# AJH_100m_ADSR_1_0.net
KiCad netlist of a schematic drawn in EAGLE
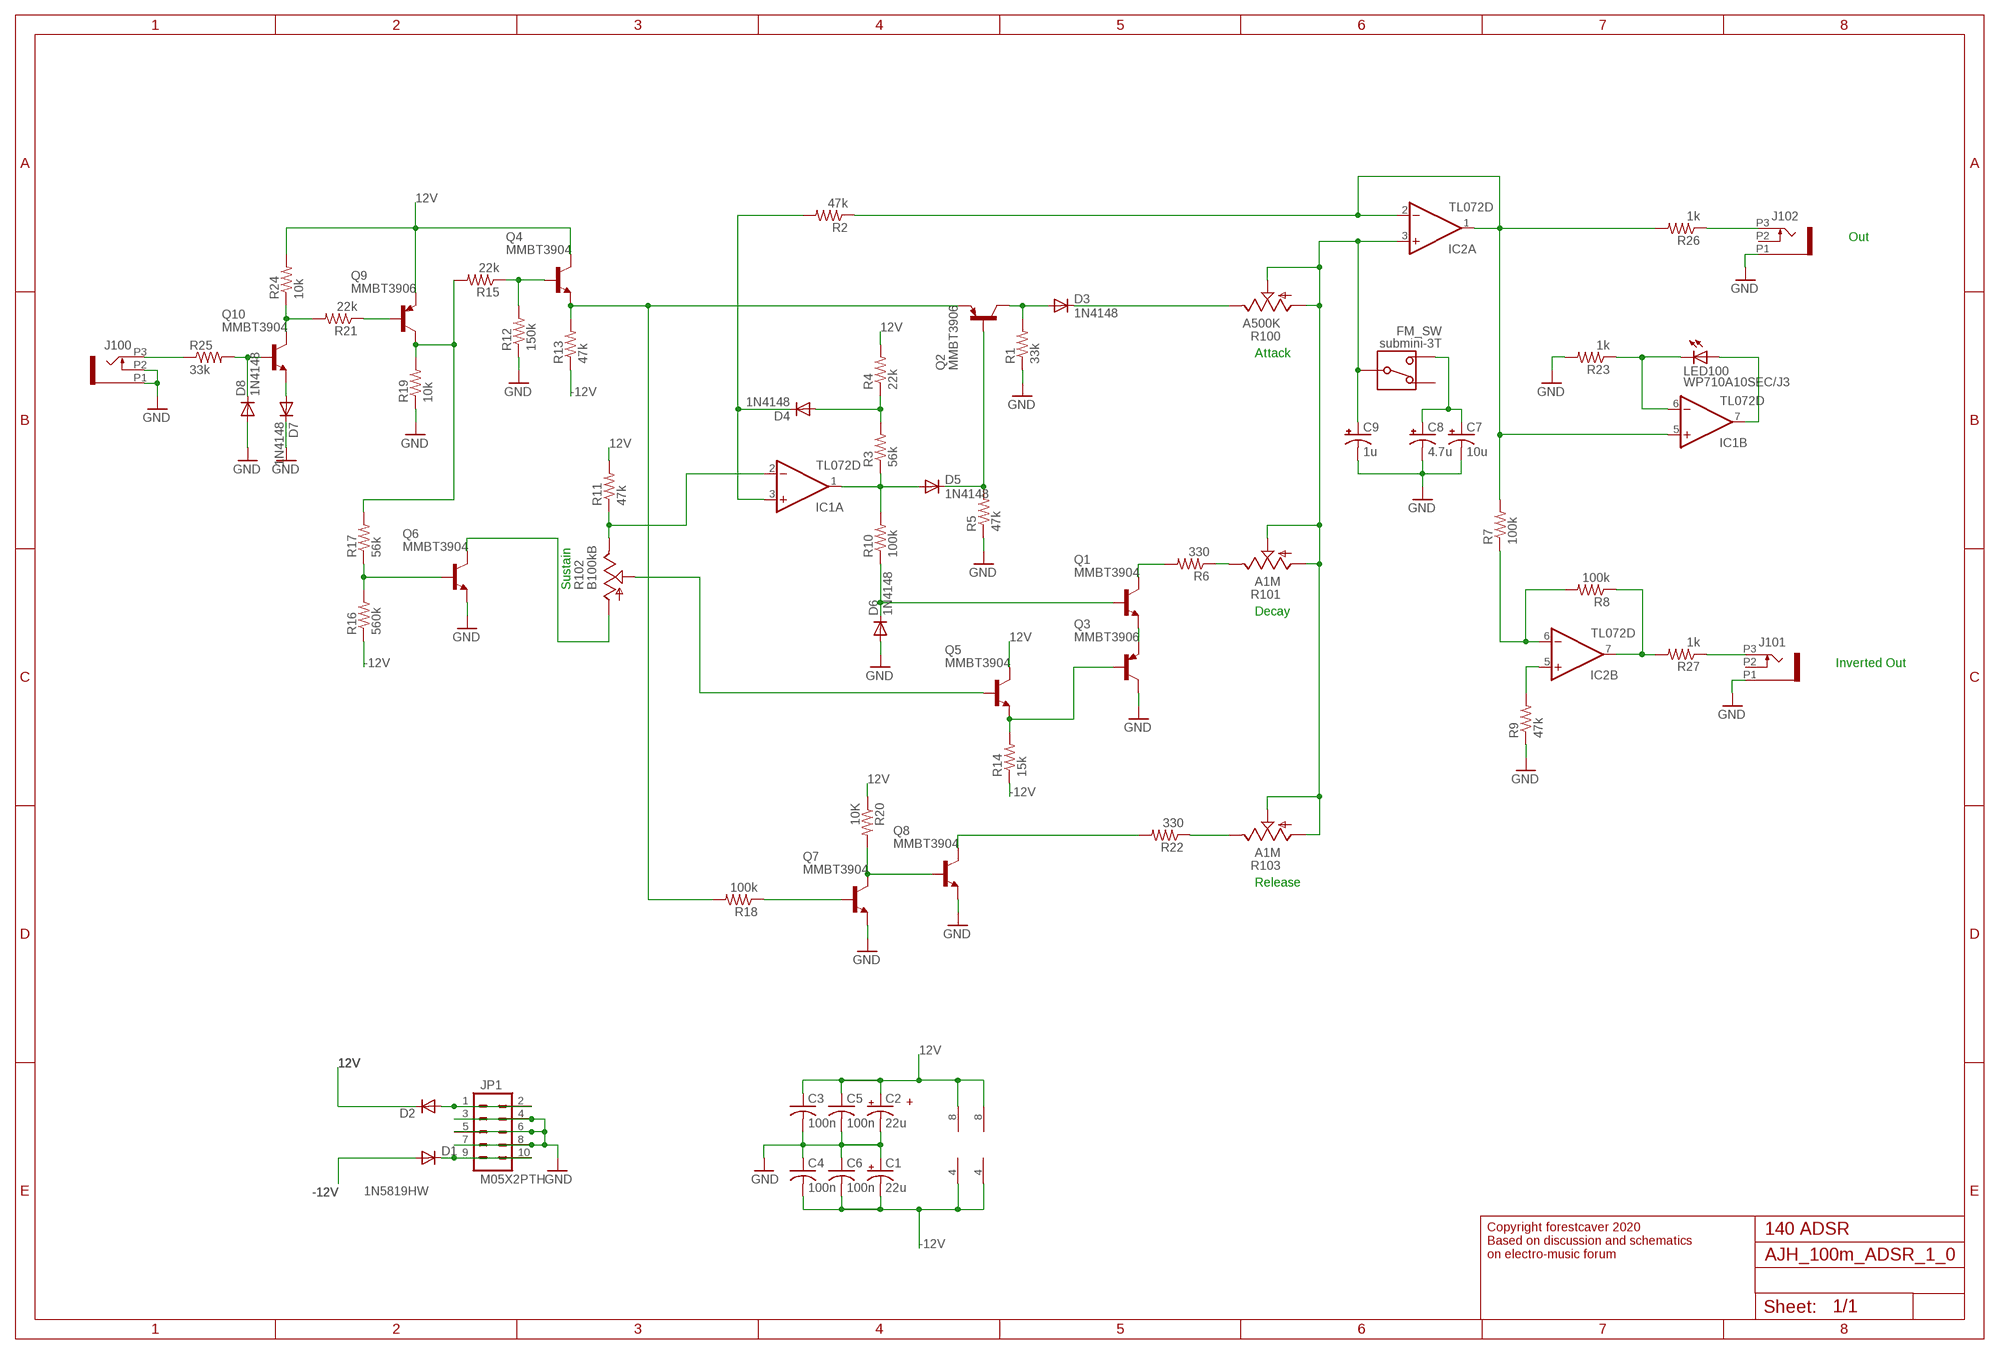
[diagram p0: schematic, sheet 1]

(export (version "E")
  (design (tool "Eeschema 10.0.6"))
  (components
    (comp (ref "C1")
      (value "22u")
      (footprint "eagle-import:PANASONIC_B")
      (libsource (lib "eagle-import") (part "CPOL-USB"))
    )
    (comp (ref "C2")
      (value "22u")
      (footprint "eagle-import:PANASONIC_B")
      (libsource (lib "eagle-import") (part "CPOL-USB"))
    )
    (comp (ref "C3")
      (value "100n")
      (footprint "eagle-import:C0603")
      (libsource (lib "eagle-import") (part "C-USC0603"))
    )
    (comp (ref "C4")
      (value "100n")
      (footprint "eagle-import:C0603")
      (libsource (lib "eagle-import") (part "C-USC0603"))
    )
    (comp (ref "C5")
      (value "100n")
      (footprint "eagle-import:C0603")
      (libsource (lib "eagle-import") (part "C-USC0603"))
    )
    (comp (ref "C6")
      (value "100n")
      (footprint "eagle-import:C0603")
      (libsource (lib "eagle-import") (part "C-USC0603"))
    )
    (comp (ref "C7")
      (value "10u")
      (footprint "eagle-import:PANASONIC_B")
      (libsource (lib "eagle-import") (part "CPOL-USB"))
    )
    (comp (ref "C8")
      (value "4.7u")
      (footprint "eagle-import:PANASONIC_B")
      (libsource (lib "eagle-import") (part "CPOL-USB"))
    )
    (comp (ref "C9")
      (value "1u")
      (footprint "eagle-import:PANASONIC_B")
      (libsource (lib "eagle-import") (part "CPOL-USB"))
    )
    (comp (ref "D1")
      (value "1N5819HW")
      (footprint "eagle-import:SOD123")
      (libsource (lib "eagle-import") (part "DIODE-SOD123"))
    )
    (comp (ref "D2")
      (value "1N5819HW")
      (footprint "eagle-import:SOD123")
      (libsource (lib "eagle-import") (part "DIODE-SOD123"))
    )
    (comp (ref "D3")
      (value "1N4148")
      (footprint "eagle-import:SOD323-W")
      (libsource (lib "eagle-import") (part "DIODE-SOD323-W"))
    )
    (comp (ref "D4")
      (value "1N4148")
      (footprint "eagle-import:SOD323-W")
      (libsource (lib "eagle-import") (part "DIODE-SOD323-W"))
    )
    (comp (ref "D5")
      (value "1N4148")
      (footprint "eagle-import:SOD323-W")
      (libsource (lib "eagle-import") (part "DIODE-SOD323-W"))
    )
    (comp (ref "D6")
      (value "1N4148")
      (footprint "eagle-import:SOD323-W")
      (libsource (lib "eagle-import") (part "DIODE-SOD323-W"))
    )
    (comp (ref "D7")
      (value "1N4148")
      (footprint "eagle-import:SOD323-W")
      (libsource (lib "eagle-import") (part "DIODE-SOD323-W"))
    )
    (comp (ref "D8")
      (value "1N4148")
      (footprint "eagle-import:SOD323-W")
      (libsource (lib "eagle-import") (part "DIODE-SOD323-W"))
    )
    (comp (ref "FM_SW")
      (value "submini-3T")
      (footprint "eagle-import:SPDT-SUB")
      (libsource (lib "eagle-import") (part "SPDTT"))
    )
    (comp (ref "IC1")
      (value "TL072D")
      (footprint "eagle-import:SO08")
      (libsource (lib "eagle-import") (part "TL072D"))
    )
    (comp (ref "IC2")
      (value "TL072D")
      (footprint "eagle-import:SO08")
      (libsource (lib "eagle-import") (part "TL072D"))
    )
    (comp (ref "J100")
      (value "PJ301_THONKICONN6")
      (footprint "eagle-import:WQP_PJ_301M6")
      (libsource (lib "eagle-import") (part "PJ301_THONKICONN6"))
    )
    (comp (ref "J101")
      (value "PJ301_THONKICONN6")
      (footprint "eagle-import:WQP_PJ_301M6")
      (libsource (lib "eagle-import") (part "PJ301_THONKICONN6"))
    )
    (comp (ref "J102")
      (value "PJ301_THONKICONN6")
      (footprint "eagle-import:WQP_PJ_301M6")
      (libsource (lib "eagle-import") (part "PJ301_THONKICONN6"))
    )
    (comp (ref "JP1")
      (value "M05X2PTH")
      (footprint "eagle-import:AVR_ICSP")
      (libsource (lib "eagle-import") (part "M05X2PTH"))
    )
    (comp (ref "LED100")
      (value "WP710A10SEC/J3")
      (footprint "eagle-import:LED3MM")
      (libsource (lib "eagle-import") (part "LED3MM"))
    )
    (comp (ref "Q1")
      (value "MMBT3904")
      (footprint "eagle-import:SOT23-BEC")
      (libsource (lib "eagle-import") (part "-NPN-SOT23-BECMMBT3904LT1"))
    )
    (comp (ref "Q2")
      (value "MMBT3906")
      (footprint "eagle-import:SOT23-BEC")
      (libsource (lib "eagle-import") (part "-PNP-SOT23-BECMMBT3906LT1"))
    )
    (comp (ref "Q3")
      (value "MMBT3906")
      (footprint "eagle-import:SOT23-BEC")
      (libsource (lib "eagle-import") (part "-PNP-SOT23-BECMMBT3906LT1"))
    )
    (comp (ref "Q4")
      (value "MMBT3904")
      (footprint "eagle-import:SOT23-BEC")
      (libsource (lib "eagle-import") (part "-NPN-SOT23-BECMMBT3904LT1"))
    )
    (comp (ref "Q5")
      (value "MMBT3904")
      (footprint "eagle-import:SOT23-BEC")
      (libsource (lib "eagle-import") (part "-NPN-SOT23-BECMMBT3904LT1"))
    )
    (comp (ref "Q6")
      (value "MMBT3904")
      (footprint "eagle-import:SOT23-BEC")
      (libsource (lib "eagle-import") (part "-NPN-SOT23-BECMMBT3904LT1"))
    )
    (comp (ref "Q7")
      (value "MMBT3904")
      (footprint "eagle-import:SOT23-BEC")
      (libsource (lib "eagle-import") (part "-NPN-SOT23-BECMMBT3904LT1"))
    )
    (comp (ref "Q8")
      (value "MMBT3904")
      (footprint "eagle-import:SOT23-BEC")
      (libsource (lib "eagle-import") (part "-NPN-SOT23-BECMMBT3904LT1"))
    )
    (comp (ref "Q9")
      (value "MMBT3906")
      (footprint "eagle-import:SOT23-BEC")
      (libsource (lib "eagle-import") (part "-PNP-SOT23-BECMMBT3906LT1"))
    )
    (comp (ref "Q10")
      (value "MMBT3904")
      (footprint "eagle-import:SOT23-BEC")
      (libsource (lib "eagle-import") (part "-NPN-SOT23-BECMMBT3904LT1"))
    )
    (comp (ref "R1")
      (value "33k")
      (footprint "eagle-import:R0603")
      (libsource (lib "eagle-import") (part "resistor_R-US_R0603"))
    )
    (comp (ref "R2")
      (value "47k")
      (footprint "eagle-import:R0603")
      (libsource (lib "eagle-import") (part "resistor_R-US_R0603"))
    )
    (comp (ref "R3")
      (value "56k")
      (footprint "eagle-import:R0603")
      (libsource (lib "eagle-import") (part "resistor_R-US_R0603"))
    )
    (comp (ref "R4")
      (value "22k")
      (footprint "eagle-import:R0603")
      (libsource (lib "eagle-import") (part "resistor_R-US_R0603"))
    )
    (comp (ref "R5")
      (value "47k")
      (footprint "eagle-import:R0603")
      (libsource (lib "eagle-import") (part "resistor_R-US_R0603"))
    )
    (comp (ref "R6")
      (value "330")
      (footprint "eagle-import:R0603")
      (libsource (lib "eagle-import") (part "resistor_R-US_R0603"))
    )
    (comp (ref "R7")
      (value "100k")
      (footprint "eagle-import:R0603")
      (libsource (lib "eagle-import") (part "resistor_R-US_R0603"))
    )
    (comp (ref "R8")
      (value "100k")
      (footprint "eagle-import:R0603")
      (libsource (lib "eagle-import") (part "resistor_R-US_R0603"))
    )
    (comp (ref "R9")
      (value "47k")
      (footprint "eagle-import:R0603")
      (libsource (lib "eagle-import") (part "resistor_R-US_R0603"))
    )
    (comp (ref "R10")
      (value "100k")
      (footprint "eagle-import:R0603")
      (libsource (lib "eagle-import") (part "resistor_R-US_R0603"))
    )
    (comp (ref "R11")
      (value "47k")
      (footprint "eagle-import:R0603")
      (libsource (lib "eagle-import") (part "resistor_R-US_R0603"))
    )
    (comp (ref "R12")
      (value "150k")
      (footprint "eagle-import:R0603")
      (libsource (lib "eagle-import") (part "resistor_R-US_R0603"))
    )
    (comp (ref "R13")
      (value "47k")
      (footprint "eagle-import:R0603")
      (libsource (lib "eagle-import") (part "resistor_R-US_R0603"))
    )
    (comp (ref "R14")
      (value "15k")
      (footprint "eagle-import:R0603")
      (libsource (lib "eagle-import") (part "resistor_R-US_R0603"))
    )
    (comp (ref "R15")
      (value "22k")
      (footprint "eagle-import:R0603")
      (libsource (lib "eagle-import") (part "resistor_R-US_R0603"))
    )
    (comp (ref "R16")
      (value "560k")
      (footprint "eagle-import:R0603")
      (libsource (lib "eagle-import") (part "resistor_R-US_R0603"))
    )
    (comp (ref "R17")
      (value "56k")
      (footprint "eagle-import:R0603")
      (libsource (lib "eagle-import") (part "resistor_R-US_R0603"))
    )
    (comp (ref "R18")
      (value "100k")
      (footprint "eagle-import:R0603")
      (libsource (lib "eagle-import") (part "resistor_R-US_R0603"))
    )
    (comp (ref "R19")
      (value "10k")
      (footprint "eagle-import:R0603")
      (libsource (lib "eagle-import") (part "resistor_R-US_R0603"))
    )
    (comp (ref "R20")
      (value "10K")
      (footprint "eagle-import:R0603")
      (libsource (lib "eagle-import") (part "resistor_R-US_R0603"))
    )
    (comp (ref "R21")
      (value "22k")
      (footprint "eagle-import:R0603")
      (libsource (lib "eagle-import") (part "resistor_R-US_R0603"))
    )
    (comp (ref "R22")
      (value "330")
      (footprint "eagle-import:R0603")
      (libsource (lib "eagle-import") (part "resistor_R-US_R0603"))
    )
    (comp (ref "R23")
      (value "1k")
      (footprint "eagle-import:R0603")
      (libsource (lib "eagle-import") (part "R-US_R0603"))
    )
    (comp (ref "R24")
      (value "10k")
      (footprint "eagle-import:R0603")
      (libsource (lib "eagle-import") (part "resistor_R-US_R0603"))
    )
    (comp (ref "R25")
      (value "33k")
      (footprint "eagle-import:R0603")
      (libsource (lib "eagle-import") (part "resistor_R-US_R0603"))
    )
    (comp (ref "R26")
      (value "1k")
      (footprint "eagle-import:R0603")
      (libsource (lib "eagle-import") (part "resistor_R-US_R0603"))
    )
    (comp (ref "R27")
      (value "1k")
      (footprint "eagle-import:R0603")
      (libsource (lib "eagle-import") (part "resistor_R-US_R0603"))
    )
    (comp (ref "R100")
      (value "A500K")
      (footprint "eagle-import:ALPS_POT_VERTICAL")
      (libsource (lib "eagle-import") (part "POT_USVERTICAL"))
    )
    (comp (ref "R101")
      (value "A1M")
      (footprint "eagle-import:ALPS_POT_VERTICAL")
      (libsource (lib "eagle-import") (part "POT_USVERTICAL"))
    )
    (comp (ref "R102")
      (value "B100kB")
      (footprint "eagle-import:ALPS_POT_VERTICAL")
      (libsource (lib "eagle-import") (part "POT_USVERTICAL"))
    )
    (comp (ref "R103")
      (value "A1M")
      (footprint "eagle-import:ALPS_POT_VERTICAL")
      (libsource (lib "eagle-import") (part "POT_USVERTICAL"))
    )
  )
  (nets
    (net (code "1") (name "/-12V") (class "Default")
      (node (ref "C1") (pin "-") (pinfunction "-_-") (pintype "passive"))
      (node (ref "C4") (pin "2") (pinfunction "2_2") (pintype "passive"))
      (node (ref "C6") (pin "2") (pinfunction "2_2") (pintype "passive"))
      (node (ref "D1") (pin "A") (pinfunction "A_A") (pintype "passive"))
      (node (ref "IC1") (pin "4") (pinfunction "V-_4") (pintype "power_in"))
      (node (ref "IC2") (pin "4") (pinfunction "V-_4") (pintype "power_in"))
      (node (ref "R13") (pin "1") (pinfunction "1_1") (pintype "passive"))
      (node (ref "R14") (pin "1") (pinfunction "1_1") (pintype "passive"))
      (node (ref "R16") (pin "1") (pinfunction "1_1") (pintype "passive"))
    )
    (net (code "2") (name "/12V") (class "Default")
      (node (ref "C2") (pin "+") (pinfunction "+_+") (pintype "passive"))
      (node (ref "C3") (pin "1") (pinfunction "1_1") (pintype "passive"))
      (node (ref "C5") (pin "1") (pinfunction "1_1") (pintype "passive"))
      (node (ref "D2") (pin "C") (pinfunction "C_C") (pintype "passive"))
      (node (ref "IC1") (pin "8") (pinfunction "V+_8") (pintype "power_in"))
      (node (ref "IC2") (pin "8") (pinfunction "V+_8") (pintype "power_in"))
      (node (ref "Q4") (pin "C") (pinfunction "C_C") (pintype "passive"))
      (node (ref "Q5") (pin "C") (pinfunction "C_C") (pintype "passive"))
      (node (ref "Q9") (pin "E") (pinfunction "E_E") (pintype "passive"))
      (node (ref "R11") (pin "2") (pinfunction "2_2") (pintype "passive"))
      (node (ref "R20") (pin "1") (pinfunction "1_1") (pintype "passive"))
      (node (ref "R24") (pin "2") (pinfunction "2_2") (pintype "passive"))
      (node (ref "R4") (pin "2") (pinfunction "2_2") (pintype "passive"))
    )
    (net (code "3") (name "GND") (class "Default")
      (node (ref "C1") (pin "+") (pinfunction "+_+") (pintype "passive"))
      (node (ref "C2") (pin "-") (pinfunction "-_-") (pintype "passive"))
      (node (ref "C3") (pin "2") (pinfunction "2_2") (pintype "passive"))
      (node (ref "C4") (pin "1") (pinfunction "1_1") (pintype "passive"))
      (node (ref "C5") (pin "2") (pinfunction "2_2") (pintype "passive"))
      (node (ref "C6") (pin "1") (pinfunction "1_1") (pintype "passive"))
      (node (ref "C7") (pin "-") (pinfunction "-_-") (pintype "passive"))
      (node (ref "C8") (pin "-") (pinfunction "-_-") (pintype "passive"))
      (node (ref "C9") (pin "-") (pinfunction "-_-") (pintype "passive"))
      (node (ref "D6") (pin "A") (pinfunction "A_A") (pintype "passive"))
      (node (ref "D7") (pin "C") (pinfunction "C_C") (pintype "passive"))
      (node (ref "D8") (pin "A") (pinfunction "A_A") (pintype "passive"))
      (node (ref "J100") (pin "P1") (pinfunction "1_P1") (pintype "passive"))
      (node (ref "J100") (pin "P2") (pinfunction "2_P2") (pintype "passive"))
      (node (ref "J101") (pin "P1") (pinfunction "1_P1") (pintype "passive"))
      (node (ref "J102") (pin "P1") (pinfunction "1_P1") (pintype "passive"))
      (node (ref "JP1") (pin "3") (pinfunction "3_3") (pintype "passive"))
      (node (ref "JP1") (pin "4") (pinfunction "4_4") (pintype "passive"))
      (node (ref "JP1") (pin "5") (pinfunction "5_5") (pintype "passive"))
      (node (ref "JP1") (pin "6") (pinfunction "6_6") (pintype "passive"))
      (node (ref "JP1") (pin "7") (pinfunction "7_7") (pintype "passive"))
      (node (ref "JP1") (pin "8") (pinfunction "8_8") (pintype "passive"))
      (node (ref "Q3") (pin "C") (pinfunction "C_C") (pintype "passive"))
      (node (ref "Q6") (pin "E") (pinfunction "E_E") (pintype "passive"))
      (node (ref "Q7") (pin "E") (pinfunction "E_E") (pintype "passive"))
      (node (ref "Q8") (pin "E") (pinfunction "E_E") (pintype "passive"))
      (node (ref "R1") (pin "1") (pinfunction "1_1") (pintype "passive"))
      (node (ref "R12") (pin "1") (pinfunction "1_1") (pintype "passive"))
      (node (ref "R19") (pin "1") (pinfunction "1_1") (pintype "passive"))
      (node (ref "R23") (pin "2") (pinfunction "2_2") (pintype "passive"))
      (node (ref "R5") (pin "1") (pinfunction "1_1") (pintype "passive"))
      (node (ref "R9") (pin "1") (pinfunction "1_1") (pintype "passive"))
    )
    (net (code "4") (name "Net-(C7-Pad+)") (class "Default")
      (node (ref "C7") (pin "+") (pinfunction "+_+") (pintype "passive"))
      (node (ref "C8") (pin "+") (pinfunction "+_+") (pintype "passive"))
      (node (ref "FM_SW") (pin "P$1") (pinfunction "P$1_P$1") (pintype "passive"))
    )
    (net (code "5") (name "Net-(D1-PadC)") (class "Default")
      (node (ref "D1") (pin "C") (pinfunction "C_C") (pintype "passive"))
      (node (ref "JP1") (pin "10") (pinfunction "10_10") (pintype "passive"))
      (node (ref "JP1") (pin "9") (pinfunction "9_9") (pintype "passive"))
    )
    (net (code "6") (name "Net-(D2-PadA)") (class "Default")
      (node (ref "D2") (pin "A") (pinfunction "A_A") (pintype "passive"))
      (node (ref "JP1") (pin "1") (pinfunction "1_1") (pintype "passive"))
      (node (ref "JP1") (pin "2") (pinfunction "2_2") (pintype "passive"))
    )
    (net (code "7") (name "Net-(D3-PadA)") (class "Default")
      (node (ref "D3") (pin "A") (pinfunction "A_A") (pintype "passive"))
      (node (ref "Q2") (pin "C") (pinfunction "C_C") (pintype "passive"))
      (node (ref "R1") (pin "2") (pinfunction "2_2") (pintype "passive"))
    )
    (net (code "8") (name "Net-(D4-PadA)") (class "Default")
      (node (ref "D4") (pin "A") (pinfunction "A_A") (pintype "passive"))
      (node (ref "R3") (pin "2") (pinfunction "2_2") (pintype "passive"))
      (node (ref "R4") (pin "1") (pinfunction "1_1") (pintype "passive"))
    )
    (net (code "9") (name "Net-(D5-PadC)") (class "Default")
      (node (ref "D5") (pin "C") (pinfunction "C_C") (pintype "passive"))
      (node (ref "Q2") (pin "B") (pinfunction "B_B") (pintype "passive"))
      (node (ref "R5") (pin "2") (pinfunction "2_2") (pintype "passive"))
    )
    (net (code "10") (name "Net-(D6-PadC)") (class "Default")
      (node (ref "D6") (pin "C") (pinfunction "C_C") (pintype "passive"))
      (node (ref "Q1") (pin "B") (pinfunction "B_B") (pintype "passive"))
      (node (ref "R10") (pin "1") (pinfunction "1_1") (pintype "passive"))
    )
    (net (code "11") (name "Net-(D7-PadA)") (class "Default")
      (node (ref "D7") (pin "A") (pinfunction "A_A") (pintype "passive"))
      (node (ref "Q10") (pin "E") (pinfunction "E_E") (pintype "passive"))
    )
    (net (code "12") (name "Net-(D8-PadC)") (class "Default")
      (node (ref "D8") (pin "C") (pinfunction "C_C") (pintype "passive"))
      (node (ref "Q10") (pin "B") (pinfunction "B_B") (pintype "passive"))
      (node (ref "R25") (pin "2") (pinfunction "2_2") (pintype "passive"))
    )
    (net (code "13") (name "Net-(IC1A-+IN)") (class "Default")
      (node (ref "D4") (pin "C") (pinfunction "C_C") (pintype "passive"))
      (node (ref "IC1") (pin "3") (pinfunction "+IN_3") (pintype "input"))
      (node (ref "R2") (pin "2") (pinfunction "2_2") (pintype "passive"))
    )
    (net (code "14") (name "Net-(IC1A--IN)") (class "Default")
      (node (ref "IC1") (pin "2") (pinfunction "-IN_2") (pintype "input"))
      (node (ref "R102") (pin "P$1") (pinfunction "E_P$1") (pintype "passive"))
      (node (ref "R11") (pin "1") (pinfunction "1_1") (pintype "passive"))
    )
    (net (code "15") (name "Net-(IC1A-OUT)") (class "Default")
      (node (ref "D5") (pin "A") (pinfunction "A_A") (pintype "passive"))
      (node (ref "IC1") (pin "1") (pinfunction "OUT_1") (pintype "output"))
      (node (ref "R10") (pin "2") (pinfunction "2_2") (pintype "passive"))
      (node (ref "R3") (pin "1") (pinfunction "1_1") (pintype "passive"))
    )
    (net (code "16") (name "Net-(IC1B-+IN)") (class "Default")
      (node (ref "IC1") (pin "5") (pinfunction "+IN_5") (pintype "input"))
      (node (ref "IC2") (pin "1") (pinfunction "OUT_1") (pintype "output"))
      (node (ref "IC2") (pin "2") (pinfunction "-IN_2") (pintype "input"))
      (node (ref "R2") (pin "1") (pinfunction "1_1") (pintype "passive"))
      (node (ref "R26") (pin "2") (pinfunction "2_2") (pintype "passive"))
      (node (ref "R7") (pin "2") (pinfunction "2_2") (pintype "passive"))
    )
    (net (code "17") (name "Net-(IC1B--IN)") (class "Default")
      (node (ref "IC1") (pin "6") (pinfunction "-IN_6") (pintype "input"))
      (node (ref "LED100") (pin "K") (pinfunction "C_K") (pintype "passive"))
      (node (ref "R23") (pin "1") (pinfunction "1_1") (pintype "passive"))
    )
    (net (code "18") (name "Net-(IC1B-OUT)") (class "Default")
      (node (ref "IC1") (pin "7") (pinfunction "OUT_7") (pintype "output"))
      (node (ref "LED100") (pin "A") (pinfunction "A_A") (pintype "passive"))
    )
    (net (code "19") (name "Net-(IC2A-+IN)") (class "Default")
      (node (ref "C9") (pin "+") (pinfunction "+_+") (pintype "passive"))
      (node (ref "FM_SW") (pin "P$2") (pinfunction "P$2_P$2") (pintype "passive"))
      (node (ref "IC2") (pin "3") (pinfunction "+IN_3") (pintype "input"))
      (node (ref "R100") (pin "P$2") (pinfunction "S_P$2") (pintype "passive"))
      (node (ref "R100") (pin "P$3") (pinfunction "A_P$3") (pintype "passive"))
      (node (ref "R101") (pin "P$2") (pinfunction "S_P$2") (pintype "passive"))
      (node (ref "R101") (pin "P$3") (pinfunction "A_P$3") (pintype "passive"))
      (node (ref "R103") (pin "P$2") (pinfunction "S_P$2") (pintype "passive"))
      (node (ref "R103") (pin "P$3") (pinfunction "A_P$3") (pintype "passive"))
    )
    (net (code "20") (name "Net-(IC2B-+IN)") (class "Default")
      (node (ref "IC2") (pin "5") (pinfunction "+IN_5") (pintype "input"))
      (node (ref "R9") (pin "2") (pinfunction "2_2") (pintype "passive"))
    )
    (net (code "21") (name "Net-(IC2B--IN)") (class "Default")
      (node (ref "IC2") (pin "6") (pinfunction "-IN_6") (pintype "input"))
      (node (ref "R7") (pin "1") (pinfunction "1_1") (pintype "passive"))
      (node (ref "R8") (pin "2") (pinfunction "2_2") (pintype "passive"))
    )
    (net (code "22") (name "Net-(IC2B-OUT)") (class "Default")
      (node (ref "IC2") (pin "7") (pinfunction "OUT_7") (pintype "output"))
      (node (ref "R27") (pin "2") (pinfunction "2_2") (pintype "passive"))
      (node (ref "R8") (pin "1") (pinfunction "1_1") (pintype "passive"))
    )
    (net (code "23") (name "Net-(J100-3)") (class "Default")
      (node (ref "J100") (pin "P3") (pinfunction "3_P3") (pintype "passive"))
      (node (ref "R25") (pin "1") (pinfunction "1_1") (pintype "passive"))
    )
    (net (code "24") (name "Net-(J101-3)") (class "Default")
      (node (ref "J101") (pin "P3") (pinfunction "3_P3") (pintype "passive"))
      (node (ref "R27") (pin "1") (pinfunction "1_1") (pintype "passive"))
    )
    (net (code "25") (name "Net-(J102-3)") (class "Default")
      (node (ref "J102") (pin "P3") (pinfunction "3_P3") (pintype "passive"))
      (node (ref "R26") (pin "1") (pinfunction "1_1") (pintype "passive"))
    )
    (net (code "26") (name "Net-(Q1-PadC)") (class "Default")
      (node (ref "Q1") (pin "C") (pinfunction "C_C") (pintype "passive"))
      (node (ref "R6") (pin "2") (pinfunction "2_2") (pintype "passive"))
    )
    (net (code "27") (name "Net-(Q1-PadE)") (class "Default")
      (node (ref "Q1") (pin "E") (pinfunction "E_E") (pintype "passive"))
      (node (ref "Q3") (pin "E") (pinfunction "E_E") (pintype "passive"))
    )
    (net (code "28") (name "Net-(Q2-PadE)") (class "Default")
      (node (ref "Q2") (pin "E") (pinfunction "E_E") (pintype "passive"))
      (node (ref "Q4") (pin "E") (pinfunction "E_E") (pintype "passive"))
      (node (ref "R13") (pin "2") (pinfunction "2_2") (pintype "passive"))
      (node (ref "R18") (pin "2") (pinfunction "2_2") (pintype "passive"))
    )
    (net (code "29") (name "Net-(Q3-PadB)") (class "Default")
      (node (ref "Q3") (pin "B") (pinfunction "B_B") (pintype "passive"))
      (node (ref "Q5") (pin "E") (pinfunction "E_E") (pintype "passive"))
      (node (ref "R14") (pin "2") (pinfunction "2_2") (pintype "passive"))
    )
    (net (code "30") (name "Net-(Q4-PadB)") (class "Default")
      (node (ref "Q4") (pin "B") (pinfunction "B_B") (pintype "passive"))
      (node (ref "R12") (pin "2") (pinfunction "2_2") (pintype "passive"))
      (node (ref "R15") (pin "1") (pinfunction "1_1") (pintype "passive"))
    )
    (net (code "31") (name "Net-(Q6-PadB)") (class "Default")
      (node (ref "Q6") (pin "B") (pinfunction "B_B") (pintype "passive"))
      (node (ref "R16") (pin "2") (pinfunction "2_2") (pintype "passive"))
      (node (ref "R17") (pin "1") (pinfunction "1_1") (pintype "passive"))
    )
    (net (code "32") (name "Net-(Q7-PadB)") (class "Default")
      (node (ref "Q7") (pin "B") (pinfunction "B_B") (pintype "passive"))
      (node (ref "R18") (pin "1") (pinfunction "1_1") (pintype "passive"))
    )
    (net (code "33") (name "Net-(Q7-PadC)") (class "Default")
      (node (ref "Q7") (pin "C") (pinfunction "C_C") (pintype "passive"))
      (node (ref "Q8") (pin "B") (pinfunction "B_B") (pintype "passive"))
      (node (ref "R20") (pin "2") (pinfunction "2_2") (pintype "passive"))
    )
    (net (code "34") (name "Net-(Q8-PadC)") (class "Default")
      (node (ref "Q8") (pin "C") (pinfunction "C_C") (pintype "passive"))
      (node (ref "R22") (pin "2") (pinfunction "2_2") (pintype "passive"))
    )
    (net (code "35") (name "Net-(Q9-PadB)") (class "Default")
      (node (ref "Q9") (pin "B") (pinfunction "B_B") (pintype "passive"))
      (node (ref "R21") (pin "1") (pinfunction "1_1") (pintype "passive"))
    )
    (net (code "36") (name "Net-(Q9-PadC)") (class "Default")
      (node (ref "Q9") (pin "C") (pinfunction "C_C") (pintype "passive"))
      (node (ref "R15") (pin "2") (pinfunction "2_2") (pintype "passive"))
      (node (ref "R17") (pin "2") (pinfunction "2_2") (pintype "passive"))
      (node (ref "R19") (pin "2") (pinfunction "2_2") (pintype "passive"))
    )
    (net (code "37") (name "Net-(Q10-PadC)") (class "Default")
      (node (ref "Q10") (pin "C") (pinfunction "C_C") (pintype "passive"))
      (node (ref "R21") (pin "2") (pinfunction "2_2") (pintype "passive"))
      (node (ref "R24") (pin "1") (pinfunction "1_1") (pintype "passive"))
    )
    (net (code "38") (name "Net-(R100-E)") (class "Default")
      (node (ref "D3") (pin "C") (pinfunction "C_C") (pintype "passive"))
      (node (ref "R100") (pin "P$1") (pinfunction "E_P$1") (pintype "passive"))
    )
    (net (code "39") (name "Net-(R101-E)") (class "Default")
      (node (ref "R101") (pin "P$1") (pinfunction "E_P$1") (pintype "passive"))
      (node (ref "R6") (pin "1") (pinfunction "1_1") (pintype "passive"))
    )
    (net (code "40") (name "Net-(R102-A)") (class "Default")
      (node (ref "Q6") (pin "C") (pinfunction "C_C") (pintype "passive"))
      (node (ref "R102") (pin "P$3") (pinfunction "A_P$3") (pintype "passive"))
    )
    (net (code "41") (name "Net-(R102-S)") (class "Default")
      (node (ref "Q5") (pin "B") (pinfunction "B_B") (pintype "passive"))
      (node (ref "R102") (pin "P$2") (pinfunction "S_P$2") (pintype "passive"))
    )
    (net (code "42") (name "Net-(R103-E)") (class "Default")
      (node (ref "R103") (pin "P$1") (pinfunction "E_P$1") (pintype "passive"))
      (node (ref "R22") (pin "1") (pinfunction "1_1") (pintype "passive"))
    )
    (net (code "43") (name "unconnected-(FM_SW-PadP$3)") (class "Default")
      (node (ref "FM_SW") (pin "P$3") (pinfunction "P$3_P$3") (pintype "passive"))
    )
    (net (code "44") (name "unconnected-(J101-2-PadP2)") (class "Default")
      (node (ref "J101") (pin "P2") (pinfunction "2_P2") (pintype "passive"))
    )
    (net (code "45") (name "unconnected-(J102-2-PadP2)") (class "Default")
      (node (ref "J102") (pin "P2") (pinfunction "2_P2") (pintype "passive"))
    )
  )
)
